# motordriver_control_board_02.net
KiCad netlist of a schematic drawn in EAGLE
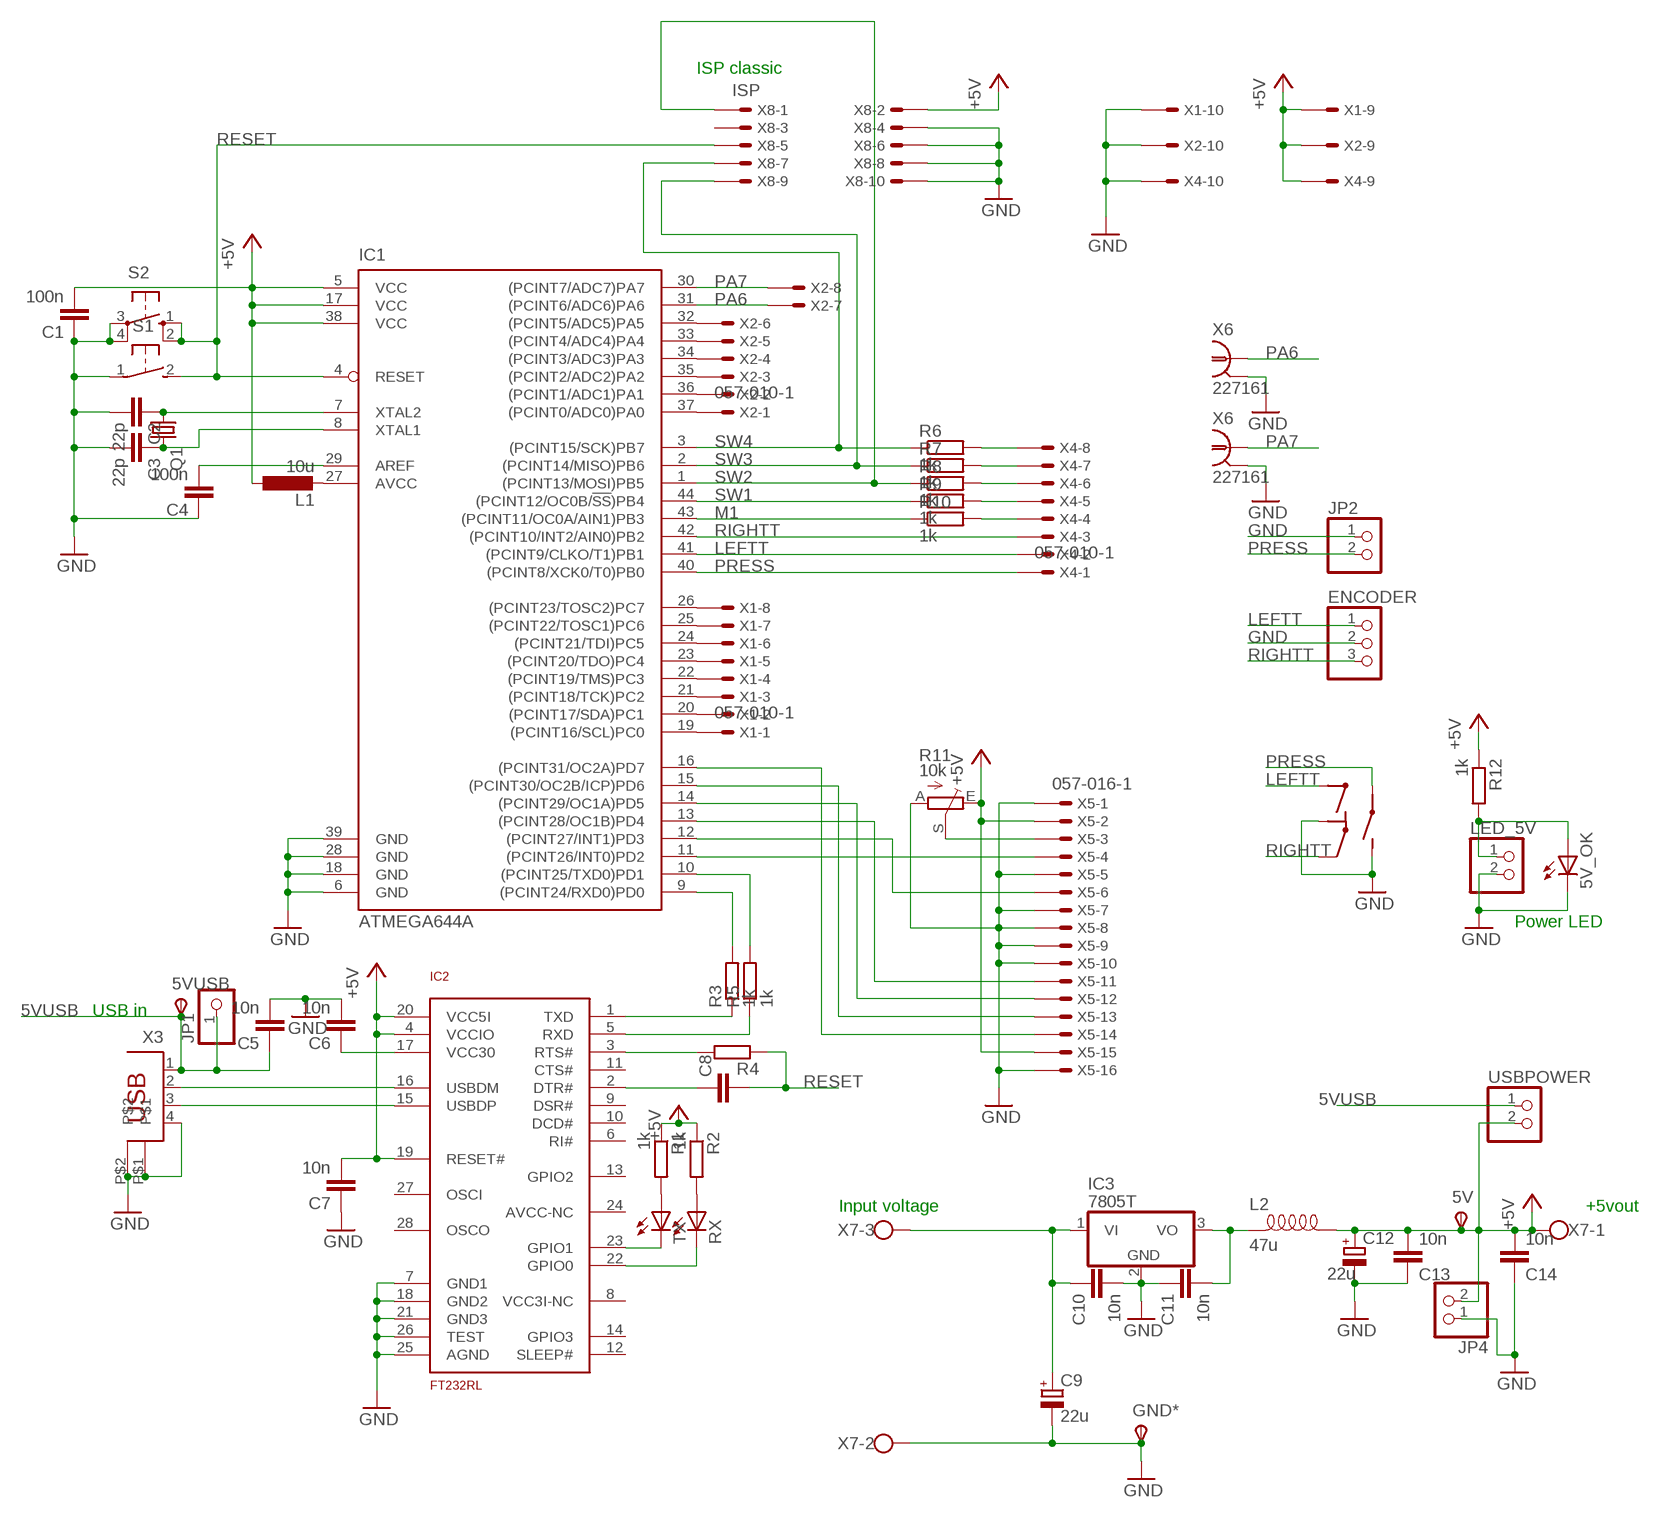
[diagram p0: schematic, sheet 1]

(export (version "E")
  (design (tool "Eeschema 10.0.6"))
  (components
    (comp (ref "5V")
      (value "TPSPAD1-13")
      (footprint "eagle-import:P1-13")
      (libsource (lib "eagle-import") (part "TPSPAD1-13"))
    )
    (comp (ref "5VUSB")
      (value "TPSPAD1-13")
      (footprint "eagle-import:P1-13")
      (libsource (lib "eagle-import") (part "TPSPAD1-13"))
    )
    (comp (ref "5V_OK")
      (value "ZURINO_LEDCHIP-LED0805")
      (footprint "eagle-import:ZURINO_CHIP-LED0805")
      (libsource (lib "eagle-import") (part "ZURINO_LEDCHIP-LED0805"))
    )
    (comp (ref "C1")
      (value "100n")
      (footprint "eagle-import:C0805")
      (libsource (lib "eagle-import") (part "C-EUC0805"))
    )
    (comp (ref "C2")
      (value "22p")
      (footprint "eagle-import:C0805")
      (libsource (lib "eagle-import") (part "C-EUC0805"))
    )
    (comp (ref "C3")
      (value "22p")
      (footprint "eagle-import:C0805")
      (libsource (lib "eagle-import") (part "C-EUC0805"))
    )
    (comp (ref "C4")
      (value "100n")
      (footprint "eagle-import:C0805")
      (libsource (lib "eagle-import") (part "C-EUC0805"))
    )
    (comp (ref "C5")
      (value "10n")
      (footprint "eagle-import:C0805")
      (libsource (lib "eagle-import") (part "C-EUC0805"))
    )
    (comp (ref "C6")
      (value "10n")
      (footprint "eagle-import:C0805")
      (libsource (lib "eagle-import") (part "C-EUC0805"))
    )
    (comp (ref "C7")
      (value "10n")
      (footprint "eagle-import:C0805")
      (libsource (lib "eagle-import") (part "C-EUC0805"))
    )
    (comp (ref "C8")
      (value "C-EUC0805")
      (footprint "eagle-import:C0805")
      (libsource (lib "eagle-import") (part "C-EUC0805"))
    )
    (comp (ref "C9")
      (value "22u")
      (footprint "eagle-import:153CLV-0605")
      (libsource (lib "eagle-import") (part "CPOL-EU153CLV-0605"))
    )
    (comp (ref "C10")
      (value "10n")
      (footprint "eagle-import:C0805")
      (libsource (lib "eagle-import") (part "C-EUC0805"))
    )
    (comp (ref "C11")
      (value "10n")
      (footprint "eagle-import:C0805")
      (libsource (lib "eagle-import") (part "C-EUC0805"))
    )
    (comp (ref "C12")
      (value "22u")
      (footprint "eagle-import:153CLV-0605")
      (libsource (lib "eagle-import") (part "CPOL-EU153CLV-0605"))
    )
    (comp (ref "C13")
      (value "10n")
      (footprint "eagle-import:C0805")
      (libsource (lib "eagle-import") (part "C-EUC0805"))
    )
    (comp (ref "C14")
      (value "10n")
      (footprint "eagle-import:C0805")
      (libsource (lib "eagle-import") (part "C-EUC0805"))
    )
    (comp (ref "ENCODER")
      (value "PINHD-1X3")
      (footprint "eagle-import:1X03")
      (libsource (lib "eagle-import") (part "PINHD-1X3"))
    )
    (comp (ref "GND*")
      (value "TPSPAD1-13")
      (footprint "eagle-import:P1-13")
      (libsource (lib "eagle-import") (part "TPSPAD1-13"))
    )
    (comp (ref "IC1")
      (value "ATMEGA644A")
      (footprint "eagle-import:TQFP44")
      (fields (field (name "MPN") "ATMEGA644PV-10AU"))
      (libsource (lib "eagle-import") (part "ATMEGA644A"))
    )
    (comp (ref "IC2")
      (value "FT232RL")
      (footprint "eagle-import:SMARTPRJ_SSOP28")
      (libsource (lib "eagle-import") (part "SMARTPRJ_FT232RL"))
    )
    (comp (ref "IC3")
      (value "7805T")
      (footprint "eagle-import:TO220H")
      (libsource (lib "eagle-import") (part "78T05"))
    )
    (comp (ref "JP1")
      (value "PINHD-1X1")
      (footprint "eagle-import:1X01")
      (libsource (lib "eagle-import") (part "PINHD-1X1"))
    )
    (comp (ref "JP2")
      (value "PINHD-1X2")
      (footprint "eagle-import:1X02")
      (libsource (lib "eagle-import") (part "PINHD-1X2"))
    )
    (comp (ref "JP4")
      (value "PINHD-1X2")
      (footprint "eagle-import:1X02")
      (libsource (lib "eagle-import") (part "PINHD-1X2"))
    )
    (comp (ref "L1")
      (value "10u")
      (footprint "eagle-import:L1812")
      (libsource (lib "eagle-import") (part "L-EUL1812"))
    )
    (comp (ref "L2")
      (value "47u")
      (footprint "eagle-import:D10F")
      (libsource (lib "eagle-import") (part "A814AY-220M"))
    )
    (comp (ref "LED_5V")
      (value "PINHD-1X2")
      (footprint "eagle-import:1X02")
      (libsource (lib "eagle-import") (part "PINHD-1X2"))
    )
    (comp (ref "Q1")
      (value "ZURINO_CRYSTALHC49UP")
      (footprint "eagle-import:ZURINO_HC49UP")
      (libsource (lib "eagle-import") (part "ZURINO_CRYSTALHC49UP"))
    )
    (comp (ref "R1")
      (value "1k")
      (footprint "eagle-import:M0805")
      (libsource (lib "eagle-import") (part "R-EU_M0805"))
    )
    (comp (ref "R2")
      (value "1k")
      (footprint "eagle-import:M0805")
      (libsource (lib "eagle-import") (part "R-EU_M0805"))
    )
    (comp (ref "R3")
      (value "1k")
      (footprint "eagle-import:M0805")
      (libsource (lib "eagle-import") (part "R-EU_M0805"))
    )
    (comp (ref "R4")
      (value "R-EU_M0805")
      (footprint "eagle-import:M0805")
      (libsource (lib "eagle-import") (part "R-EU_M0805"))
    )
    (comp (ref "R5")
      (value "1k")
      (footprint "eagle-import:M0805")
      (libsource (lib "eagle-import") (part "R-EU_M0805"))
    )
    (comp (ref "R6")
      (value "1k")
      (footprint "eagle-import:M0805")
      (libsource (lib "eagle-import") (part "R-EU_M0805"))
    )
    (comp (ref "R7")
      (value "1k")
      (footprint "eagle-import:M0805")
      (libsource (lib "eagle-import") (part "R-EU_M0805"))
    )
    (comp (ref "R8")
      (value "1k")
      (footprint "eagle-import:M0805")
      (libsource (lib "eagle-import") (part "R-EU_M0805"))
    )
    (comp (ref "R9")
      (value "1k")
      (footprint "eagle-import:M0805")
      (libsource (lib "eagle-import") (part "R-EU_M0805"))
    )
    (comp (ref "R10")
      (value "1k")
      (footprint "eagle-import:M0805")
      (libsource (lib "eagle-import") (part "R-EU_M0805"))
    )
    (comp (ref "R11")
      (value "10k")
      (footprint "eagle-import:B64Y")
      (libsource (lib "eagle-import") (part "TRIM_EU-B64Y"))
    )
    (comp (ref "R12")
      (value "1k")
      (footprint "eagle-import:M0805")
      (libsource (lib "eagle-import") (part "R-EU_M0805"))
    )
    (comp (ref "RX")
      (value "ZURINO_LEDCHIP-LED0805")
      (footprint "eagle-import:ZURINO_CHIP-LED0805")
      (libsource (lib "eagle-import") (part "ZURINO_LEDCHIP-LED0805"))
    )
    (comp (ref "S1")
      (value "ZURINO_31-XX")
      (footprint "eagle-import:ZURINO_OMRON_SW")
      (libsource (lib "eagle-import") (part "ZURINO_31-XX"))
    )
    (comp (ref "S2")
      (value "10-XX")
      (footprint "eagle-import:B3F-10XX")
      (fields (field (name "MPN") "B3F-1000"))
      (libsource (lib "eagle-import") (part "10-XX"))
    )
    (comp (ref "TX")
      (value "ZURINO_LEDCHIP-LED0805")
      (footprint "eagle-import:ZURINO_CHIP-LED0805")
      (libsource (lib "eagle-import") (part "ZURINO_LEDCHIP-LED0805"))
    )
    (comp (ref "U$1")
      (value "ENCODERW")
      (footprint "eagle-import:DREHENC")
      (libsource (lib "eagle-import") (part "ENCODERW"))
    )
    (comp (ref "USBPOWER")
      (value "PINHD-1X2")
      (footprint "eagle-import:1X02")
      (libsource (lib "eagle-import") (part "PINHD-1X2"))
    )
    (comp (ref "X1")
      (value "057-010-1")
      (footprint "eagle-import:057-010-1")
      (libsource (lib "eagle-import") (part "057-010-1"))
    )
    (comp (ref "X2")
      (value "057-010-1")
      (footprint "eagle-import:057-010-1")
      (libsource (lib "eagle-import") (part "057-010-1"))
    )
    (comp (ref "X3")
      (value "SMARTPRJ_PN61729")
      (footprint "eagle-import:SMARTPRJ_PN61729")
      (libsource (lib "eagle-import") (part "SMARTPRJ_PN61729"))
    )
    (comp (ref "X4")
      (value "057-010-1")
      (footprint "eagle-import:057-010-1")
      (libsource (lib "eagle-import") (part "057-010-1"))
    )
    (comp (ref "X5")
      (value "057-016-1")
      (footprint "eagle-import:057-016-1")
      (libsource (lib "eagle-import") (part "057-016-1"))
    )
    (comp (ref "X6")
      (value "227161")
      (footprint "eagle-import:AMP_227161")
      (libsource (lib "eagle-import") (part "227161"))
    )
    (comp (ref "X7")
      (value "W237-103")
      (footprint "eagle-import:W237-103")
      (fields (field (name "MPN") "237-103"))
      (libsource (lib "eagle-import") (part "W237-103"))
    )
    (comp (ref "X8")
      (value "ISP")
      (footprint "eagle-import:057-010-1")
      (libsource (lib "eagle-import") (part "057-010-1"))
    )
  )
  (nets
    (net (code "1") (name "+5V") (class "Default")
      (node (ref "5V") (pin "TP") (pinfunction "PP_TP") (pintype "input"))
      (node (ref "C1") (pin "2") (pinfunction "2_2") (pintype "passive"))
      (node (ref "C12") (pin "+") (pinfunction "+_+") (pintype "passive"))
      (node (ref "C13") (pin "2") (pinfunction "2_2") (pintype "passive"))
      (node (ref "C14") (pin "2") (pinfunction "2_2") (pintype "passive"))
      (node (ref "C7") (pin "2") (pinfunction "2_2") (pintype "passive"))
      (node (ref "IC1") (pin "17") (pinfunction "VCC_17") (pintype "power_in"))
      (node (ref "IC1") (pin "38") (pinfunction "VCC_38") (pintype "power_in"))
      (node (ref "IC1") (pin "5") (pinfunction "VCC_5") (pintype "power_in"))
      (node (ref "IC2") (pin "19") (pinfunction "RESET#_19") (pintype "input"))
      (node (ref "IC2") (pin "20") (pinfunction "VCC5I_20") (pintype "power_in"))
      (node (ref "IC2") (pin "4") (pinfunction "VCCIO_4") (pintype "power_in"))
      (node (ref "JP4") (pin "2") (pinfunction "2_2") (pintype "passive"))
      (node (ref "L1") (pin "1") (pinfunction "1_1") (pintype "passive"))
      (node (ref "L2") (pin "2") (pinfunction "2_2") (pintype "passive"))
      (node (ref "R1") (pin "1") (pinfunction "1_1") (pintype "passive"))
      (node (ref "R11") (pin "E") (pinfunction "E_E") (pintype "passive"))
      (node (ref "R12") (pin "1") (pinfunction "1_1") (pintype "passive"))
      (node (ref "R2") (pin "1") (pinfunction "1_1") (pintype "passive"))
      (node (ref "USBPOWER") (pin "2") (pinfunction "2_2") (pintype "passive"))
      (node (ref "X1") (pin "9") (pinfunction "S_9") (pintype "passive"))
      (node (ref "X2") (pin "9") (pinfunction "S_9") (pintype "passive"))
      (node (ref "X4") (pin "9") (pinfunction "S_9") (pintype "passive"))
      (node (ref "X5") (pin "15") (pinfunction "S_15") (pintype "passive"))
      (node (ref "X5") (pin "2") (pinfunction "S_2") (pintype "passive"))
      (node (ref "X7") (pin "1") (pinfunction "KL_1") (pintype "passive"))
      (node (ref "X8") (pin "2") (pinfunction "S_2") (pintype "passive"))
    )
    (net (code "2") (name "/5VUSB") (class "Default")
      (node (ref "5VUSB") (pin "TP") (pinfunction "PP_TP") (pintype "input"))
      (node (ref "C5") (pin "1") (pinfunction "1_1") (pintype "passive"))
      (node (ref "JP1") (pin "1") (pinfunction "1_1") (pintype "passive"))
      (node (ref "USBPOWER") (pin "1") (pinfunction "1_1") (pintype "passive"))
      (node (ref "X3") (pin "1") (pinfunction "1_1") (pintype "bidirectional"))
    )
    (net (code "3") (name "/LEFTT") (class "Default")
      (node (ref "ENCODER") (pin "1") (pinfunction "1_1") (pintype "passive"))
      (node (ref "IC1") (pin "41") (pinfunction "(PCINT9/CLKO/T1)PB1_41") (pintype "bidirectional"))
      (node (ref "U$1") (pin "P$1") (pinfunction "P$2_P$1") (pintype "bidirectional"))
      (node (ref "X4") (pin "2") (pinfunction "S_2") (pintype "passive"))
    )
    (net (code "4") (name "/M1") (class "Default")
      (node (ref "IC1") (pin "43") (pinfunction "(PCINT11/OC0A/AIN1)PB3_43") (pintype "bidirectional"))
      (node (ref "R10") (pin "1") (pinfunction "1_1") (pintype "passive"))
    )
    (net (code "5") (name "/PA6") (class "Default")
      (node (ref "IC1") (pin "31") (pinfunction "(PCINT6/ADC6)PA6_31") (pintype "bidirectional"))
      (node (ref "X2") (pin "7") (pinfunction "S_7") (pintype "passive"))
      (node (ref "X6") (pin "1") (pinfunction "1_1") (pintype "passive"))
    )
    (net (code "6") (name "/PA7") (class "Default")
      (node (ref "IC1") (pin "30") (pinfunction "(PCINT7/ADC7)PA7_30") (pintype "bidirectional"))
      (node (ref "X2") (pin "8") (pinfunction "S_8") (pintype "passive"))
      (node (ref "X6") (pin "2") (pinfunction "2_2") (pintype "passive"))
    )
    (net (code "7") (name "/PRESS") (class "Default")
      (node (ref "IC1") (pin "40") (pinfunction "(PCINT8/XCK0/T0)PB0_40") (pintype "bidirectional"))
      (node (ref "JP2") (pin "2") (pinfunction "2_2") (pintype "passive"))
      (node (ref "U$1") (pin "P$4") (pinfunction "P$4_P$4") (pintype "bidirectional"))
      (node (ref "X4") (pin "1") (pinfunction "S_1") (pintype "passive"))
    )
    (net (code "8") (name "/RESET") (class "Default")
      (node (ref "C8") (pin "2") (pinfunction "2_2") (pintype "passive"))
      (node (ref "IC1") (pin "4") (pinfunction "RESET_4") (pintype "input"))
      (node (ref "R4") (pin "1") (pinfunction "1_1") (pintype "passive"))
      (node (ref "S1") (pin "2") (pinfunction "S_2") (pintype "passive"))
      (node (ref "S2") (pin "1") (pinfunction "S_1") (pintype "passive"))
      (node (ref "S2") (pin "2") (pinfunction "S1_2") (pintype "passive"))
      (node (ref "X8") (pin "5") (pinfunction "S_5") (pintype "passive"))
    )
    (net (code "9") (name "/RIGHTT") (class "Default")
      (node (ref "ENCODER") (pin "3") (pinfunction "3_3") (pintype "passive"))
      (node (ref "IC1") (pin "42") (pinfunction "(PCINT10/INT2/AIN0)PB2_42") (pintype "bidirectional"))
      (node (ref "U$1") (pin "P$3") (pinfunction "P$3_P$3") (pintype "bidirectional"))
      (node (ref "X4") (pin "3") (pinfunction "S_3") (pintype "passive"))
    )
    (net (code "10") (name "/SW1") (class "Default")
      (node (ref "IC1") (pin "44") (pinfunction "(PCINT12/OC0B/~{SS})PB4_44") (pintype "bidirectional"))
      (node (ref "R9") (pin "1") (pinfunction "1_1") (pintype "passive"))
    )
    (net (code "11") (name "/SW2") (class "Default")
      (node (ref "IC1") (pin "1") (pinfunction "(PCINT13/MOSI)PB5_1") (pintype "bidirectional"))
      (node (ref "R8") (pin "1") (pinfunction "1_1") (pintype "passive"))
      (node (ref "X8") (pin "1") (pinfunction "S_1") (pintype "passive"))
    )
    (net (code "12") (name "/SW3") (class "Default")
      (node (ref "IC1") (pin "2") (pinfunction "(PCINT14/MISO)PB6_2") (pintype "bidirectional"))
      (node (ref "R7") (pin "1") (pinfunction "1_1") (pintype "passive"))
      (node (ref "X8") (pin "9") (pinfunction "S_9") (pintype "passive"))
    )
    (net (code "13") (name "/SW4") (class "Default")
      (node (ref "IC1") (pin "3") (pinfunction "(PCINT15/SCK)PB7_3") (pintype "bidirectional"))
      (node (ref "R6") (pin "1") (pinfunction "1_1") (pintype "passive"))
      (node (ref "X8") (pin "7") (pinfunction "S_7") (pintype "passive"))
    )
    (net (code "14") (name "GND") (class "Default")
      (node (ref "5V_OK") (pin "C") (pinfunction "C_C") (pintype "passive"))
      (node (ref "C1") (pin "1") (pinfunction "1_1") (pintype "passive"))
      (node (ref "C10") (pin "2") (pinfunction "2_2") (pintype "passive"))
      (node (ref "C11") (pin "1") (pinfunction "1_1") (pintype "passive"))
      (node (ref "C12") (pin "-") (pinfunction "-_-") (pintype "passive"))
      (node (ref "C13") (pin "1") (pinfunction "1_1") (pintype "passive"))
      (node (ref "C14") (pin "1") (pinfunction "1_1") (pintype "passive"))
      (node (ref "C2") (pin "2") (pinfunction "2_2") (pintype "passive"))
      (node (ref "C3") (pin "2") (pinfunction "2_2") (pintype "passive"))
      (node (ref "C4") (pin "1") (pinfunction "1_1") (pintype "passive"))
      (node (ref "C5") (pin "2") (pinfunction "2_2") (pintype "passive"))
      (node (ref "C6") (pin "2") (pinfunction "2_2") (pintype "passive"))
      (node (ref "C7") (pin "1") (pinfunction "1_1") (pintype "passive"))
      (node (ref "C9") (pin "-") (pinfunction "-_-") (pintype "passive"))
      (node (ref "ENCODER") (pin "2") (pinfunction "2_2") (pintype "passive"))
      (node (ref "GND*") (pin "TP") (pinfunction "PP_TP") (pintype "input"))
      (node (ref "IC1") (pin "18") (pinfunction "GND_18") (pintype "power_in"))
      (node (ref "IC1") (pin "28") (pinfunction "GND_28") (pintype "power_in"))
      (node (ref "IC1") (pin "39") (pinfunction "GND_39") (pintype "power_in"))
      (node (ref "IC1") (pin "6") (pinfunction "GND_6") (pintype "power_in"))
      (node (ref "IC2") (pin "18") (pinfunction "GND2_18") (pintype "power_in"))
      (node (ref "IC2") (pin "21") (pinfunction "GND3_21") (pintype "power_in"))
      (node (ref "IC2") (pin "25") (pinfunction "AGND_25") (pintype "power_in"))
      (node (ref "IC2") (pin "26") (pinfunction "TEST_26") (pintype "input"))
      (node (ref "IC2") (pin "7") (pinfunction "GND1_7") (pintype "power_in"))
      (node (ref "IC3") (pin "2") (pinfunction "GND_2") (pintype "passive"))
      (node (ref "JP2") (pin "1") (pinfunction "1_1") (pintype "passive"))
      (node (ref "JP4") (pin "1") (pinfunction "1_1") (pintype "passive"))
      (node (ref "LED_5V") (pin "2") (pinfunction "2_2") (pintype "passive"))
      (node (ref "R11") (pin "A") (pinfunction "A_A") (pintype "passive"))
      (node (ref "S1") (pin "1") (pinfunction "P_1") (pintype "passive"))
      (node (ref "S2") (pin "3") (pinfunction "P_3") (pintype "passive"))
      (node (ref "S2") (pin "4") (pinfunction "P1_4") (pintype "passive"))
      (node (ref "U$1") (pin "P$2") (pinfunction "P$1_P$2") (pintype "bidirectional"))
      (node (ref "U$1") (pin "P$5") (pinfunction "P$5_P$5") (pintype "bidirectional"))
      (node (ref "X1") (pin "10") (pinfunction "S_10") (pintype "passive"))
      (node (ref "X2") (pin "10") (pinfunction "S_10") (pintype "passive"))
      (node (ref "X3") (pin "4") (pinfunction "4_4") (pintype "bidirectional"))
      (node (ref "X3") (pin "P$1") (pinfunction "P$1_P$1") (pintype "bidirectional"))
      (node (ref "X3") (pin "P$2") (pinfunction "P$2_P$2") (pintype "bidirectional"))
      (node (ref "X4") (pin "10") (pinfunction "S_10") (pintype "passive"))
      (node (ref "X5") (pin "1") (pinfunction "S_1") (pintype "passive"))
      (node (ref "X5") (pin "10") (pinfunction "S_10") (pintype "passive"))
      (node (ref "X5") (pin "16") (pinfunction "S_16") (pintype "passive"))
      (node (ref "X5") (pin "5") (pinfunction "S_5") (pintype "passive"))
      (node (ref "X5") (pin "7") (pinfunction "S_7") (pintype "passive"))
      (node (ref "X5") (pin "8") (pinfunction "S_8") (pintype "passive"))
      (node (ref "X5") (pin "9") (pinfunction "S_9") (pintype "passive"))
      (node (ref "X6") (pin "1_GND") (pinfunction "1_GND_1_GND") (pintype "passive"))
      (node (ref "X6") (pin "2_GND") (pinfunction "2_GND_2_GND") (pintype "passive"))
      (node (ref "X7") (pin "2") (pinfunction "KL_2") (pintype "passive"))
      (node (ref "X8") (pin "10") (pinfunction "S_10") (pintype "passive"))
      (node (ref "X8") (pin "4") (pinfunction "S_4") (pintype "passive"))
      (node (ref "X8") (pin "6") (pinfunction "S_6") (pintype "passive"))
      (node (ref "X8") (pin "8") (pinfunction "S_8") (pintype "passive"))
    )
    (net (code "15") (name "Net-(5V_OK-PadA)") (class "Default")
      (node (ref "5V_OK") (pin "A") (pinfunction "A_A") (pintype "passive"))
      (node (ref "LED_5V") (pin "1") (pinfunction "1_1") (pintype "passive"))
      (node (ref "R12") (pin "2") (pinfunction "2_2") (pintype "passive"))
    )
    (net (code "16") (name "Net-(IC1-(PCINT0{slash}ADC0)PA0)") (class "Default")
      (node (ref "IC1") (pin "37") (pinfunction "(PCINT0/ADC0)PA0_37") (pintype "bidirectional"))
      (node (ref "X2") (pin "1") (pinfunction "S_1") (pintype "passive"))
    )
    (net (code "17") (name "Net-(IC1-(PCINT1{slash}ADC1)PA1)") (class "Default")
      (node (ref "IC1") (pin "36") (pinfunction "(PCINT1/ADC1)PA1_36") (pintype "bidirectional"))
      (node (ref "X2") (pin "2") (pinfunction "S_2") (pintype "passive"))
    )
    (net (code "18") (name "Net-(IC1-(PCINT2{slash}ADC2)PA2)") (class "Default")
      (node (ref "IC1") (pin "35") (pinfunction "(PCINT2/ADC2)PA2_35") (pintype "bidirectional"))
      (node (ref "X2") (pin "3") (pinfunction "S_3") (pintype "passive"))
    )
    (net (code "19") (name "Net-(IC1-(PCINT3{slash}ADC3)PA3)") (class "Default")
      (node (ref "IC1") (pin "34") (pinfunction "(PCINT3/ADC3)PA3_34") (pintype "bidirectional"))
      (node (ref "X2") (pin "4") (pinfunction "S_4") (pintype "passive"))
    )
    (net (code "20") (name "Net-(IC1-(PCINT4{slash}ADC4)PA4)") (class "Default")
      (node (ref "IC1") (pin "33") (pinfunction "(PCINT4/ADC4)PA4_33") (pintype "bidirectional"))
      (node (ref "X2") (pin "5") (pinfunction "S_5") (pintype "passive"))
    )
    (net (code "21") (name "Net-(IC1-(PCINT5{slash}ADC5)PA5)") (class "Default")
      (node (ref "IC1") (pin "32") (pinfunction "(PCINT5/ADC5)PA5_32") (pintype "bidirectional"))
      (node (ref "X2") (pin "6") (pinfunction "S_6") (pintype "passive"))
    )
    (net (code "22") (name "Net-(IC1-(PCINT16{slash}SCL)PC0)") (class "Default")
      (node (ref "IC1") (pin "19") (pinfunction "(PCINT16/SCL)PC0_19") (pintype "output"))
      (node (ref "X1") (pin "1") (pinfunction "S_1") (pintype "passive"))
    )
    (net (code "23") (name "Net-(IC1-(PCINT17{slash}SDA)PC1)") (class "Default")
      (node (ref "IC1") (pin "20") (pinfunction "(PCINT17/SDA)PC1_20") (pintype "output"))
      (node (ref "X1") (pin "2") (pinfunction "S_2") (pintype "passive"))
    )
    (net (code "24") (name "Net-(IC1-(PCINT18{slash}TCK)PC2)") (class "Default")
      (node (ref "IC1") (pin "21") (pinfunction "(PCINT18/TCK)PC2_21") (pintype "output"))
      (node (ref "X1") (pin "3") (pinfunction "S_3") (pintype "passive"))
    )
    (net (code "25") (name "Net-(IC1-(PCINT19{slash}TMS)PC3)") (class "Default")
      (node (ref "IC1") (pin "22") (pinfunction "(PCINT19/TMS)PC3_22") (pintype "output"))
      (node (ref "X1") (pin "4") (pinfunction "S_4") (pintype "passive"))
    )
    (net (code "26") (name "Net-(IC1-(PCINT20{slash}TDO)PC4)") (class "Default")
      (node (ref "IC1") (pin "23") (pinfunction "(PCINT20/TDO)PC4_23") (pintype "output"))
      (node (ref "X1") (pin "5") (pinfunction "S_5") (pintype "passive"))
    )
    (net (code "27") (name "Net-(IC1-(PCINT21{slash}TDI)PC5)") (class "Default")
      (node (ref "IC1") (pin "24") (pinfunction "(PCINT21/TDI)PC5_24") (pintype "output"))
      (node (ref "X1") (pin "6") (pinfunction "S_6") (pintype "passive"))
    )
    (net (code "28") (name "Net-(IC1-(PCINT22{slash}TOSC1)PC6)") (class "Default")
      (node (ref "IC1") (pin "25") (pinfunction "(PCINT22/TOSC1)PC6_25") (pintype "output"))
      (node (ref "X1") (pin "7") (pinfunction "S_7") (pintype "passive"))
    )
    (net (code "29") (name "Net-(IC1-(PCINT23{slash}TOSC2)PC7)") (class "Default")
      (node (ref "IC1") (pin "26") (pinfunction "(PCINT23/TOSC2)PC7_26") (pintype "output"))
      (node (ref "X1") (pin "8") (pinfunction "S_8") (pintype "passive"))
    )
    (net (code "30") (name "Net-(IC1-(PCINT24{slash}RXD0)PD0)") (class "Default")
      (node (ref "IC1") (pin "9") (pinfunction "(PCINT24/RXD0)PD0_9") (pintype "bidirectional"))
      (node (ref "R3") (pin "2") (pinfunction "2_2") (pintype "passive"))
    )
    (net (code "31") (name "Net-(IC1-(PCINT25{slash}TXD0)PD1)") (class "Default")
      (node (ref "IC1") (pin "10") (pinfunction "(PCINT25/TXD0)PD1_10") (pintype "bidirectional"))
      (node (ref "R5") (pin "2") (pinfunction "2_2") (pintype "passive"))
    )
    (net (code "32") (name "Net-(IC1-(PCINT26{slash}INT0)PD2)") (class "Default")
      (node (ref "IC1") (pin "11") (pinfunction "(PCINT26/INT0)PD2_11") (pintype "bidirectional"))
      (node (ref "X5") (pin "4") (pinfunction "S_4") (pintype "passive"))
    )
    (net (code "33") (name "Net-(IC1-(PCINT27{slash}INT1)PD3)") (class "Default")
      (node (ref "IC1") (pin "12") (pinfunction "(PCINT27/INT1)PD3_12") (pintype "bidirectional"))
      (node (ref "X5") (pin "6") (pinfunction "S_6") (pintype "passive"))
    )
    (net (code "34") (name "Net-(IC1-(PCINT28{slash}OC1B)PD4)") (class "Default")
      (node (ref "IC1") (pin "13") (pinfunction "(PCINT28/OC1B)PD4_13") (pintype "bidirectional"))
      (node (ref "X5") (pin "11") (pinfunction "S_11") (pintype "passive"))
    )
    (net (code "35") (name "Net-(IC1-(PCINT29{slash}OC1A)PD5)") (class "Default")
      (node (ref "IC1") (pin "14") (pinfunction "(PCINT29/OC1A)PD5_14") (pintype "bidirectional"))
      (node (ref "X5") (pin "12") (pinfunction "S_12") (pintype "passive"))
    )
    (net (code "36") (name "Net-(IC1-(PCINT30{slash}OC2B{slash}ICP)PD6)") (class "Default")
      (node (ref "IC1") (pin "15") (pinfunction "(PCINT30/OC2B/ICP)PD6_15") (pintype "bidirectional"))
      (node (ref "X5") (pin "13") (pinfunction "S_13") (pintype "passive"))
    )
    (net (code "37") (name "Net-(IC1-(PCINT31{slash}OC2A)PD7)") (class "Default")
      (node (ref "IC1") (pin "16") (pinfunction "(PCINT31/OC2A)PD7_16") (pintype "bidirectional"))
      (node (ref "X5") (pin "14") (pinfunction "S_14") (pintype "passive"))
    )
    (net (code "38") (name "Net-(IC1-AREF)") (class "Default")
      (node (ref "C4") (pin "2") (pinfunction "2_2") (pintype "passive"))
      (node (ref "IC1") (pin "29") (pinfunction "AREF_29") (pintype "passive"))
    )
    (net (code "39") (name "Net-(IC1-AVCC)") (class "Default")
      (node (ref "IC1") (pin "27") (pinfunction "AVCC_27") (pintype "power_in"))
      (node (ref "L1") (pin "2") (pinfunction "2_2") (pintype "passive"))
    )
    (net (code "40") (name "Net-(IC1-XTAL1)") (class "Default")
      (node (ref "C3") (pin "1") (pinfunction "1_1") (pintype "passive"))
      (node (ref "IC1") (pin "8") (pinfunction "XTAL1_8") (pintype "bidirectional"))
      (node (ref "Q1") (pin "2") (pinfunction "2_2") (pintype "passive"))
    )
    (net (code "41") (name "Net-(IC1-XTAL2)") (class "Default")
      (node (ref "C2") (pin "1") (pinfunction "1_1") (pintype "passive"))
      (node (ref "IC1") (pin "7") (pinfunction "XTAL2_7") (pintype "bidirectional"))
      (node (ref "Q1") (pin "1") (pinfunction "1_1") (pintype "passive"))
    )
    (net (code "42") (name "Net-(IC2-DTR#)") (class "Default")
      (node (ref "C8") (pin "1") (pinfunction "1_1") (pintype "passive"))
      (node (ref "IC2") (pin "2") (pinfunction "DTR#_2") (pintype "output"))
    )
    (net (code "43") (name "Net-(IC2-GPIO0)") (class "Default")
      (node (ref "IC2") (pin "22") (pinfunction "GPIO0_22") (pintype "output"))
      (node (ref "RX") (pin "C") (pinfunction "C_C") (pintype "passive"))
    )
    (net (code "44") (name "Net-(IC2-GPIO1)") (class "Default")
      (node (ref "IC2") (pin "23") (pinfunction "GPIO1_23") (pintype "output"))
      (node (ref "TX") (pin "C") (pinfunction "C_C") (pintype "passive"))
    )
    (net (code "45") (name "Net-(IC2-RTS#)") (class "Default")
      (node (ref "IC2") (pin "3") (pinfunction "RTS#_3") (pintype "output"))
      (node (ref "R4") (pin "2") (pinfunction "2_2") (pintype "passive"))
    )
    (net (code "46") (name "Net-(IC2-RXD)") (class "Default")
      (node (ref "IC2") (pin "5") (pinfunction "RXD_5") (pintype "input"))
      (node (ref "R5") (pin "1") (pinfunction "1_1") (pintype "passive"))
    )
    (net (code "47") (name "Net-(IC2-TXD)") (class "Default")
      (node (ref "IC2") (pin "1") (pinfunction "TXD_1") (pintype "output"))
      (node (ref "R3") (pin "1") (pinfunction "1_1") (pintype "passive"))
    )
    (net (code "48") (name "Net-(IC2-USBDM)") (class "Default")
      (node (ref "IC2") (pin "16") (pinfunction "USBDM_16") (pintype "bidirectional"))
      (node (ref "X3") (pin "2") (pinfunction "2_2") (pintype "bidirectional"))
    )
    (net (code "49") (name "Net-(IC2-USBDP)") (class "Default")
      (node (ref "IC2") (pin "15") (pinfunction "USBDP_15") (pintype "bidirectional"))
      (node (ref "X3") (pin "3") (pinfunction "3_3") (pintype "bidirectional"))
    )
    (net (code "50") (name "Net-(IC2-VCC30)") (class "Default")
      (node (ref "C6") (pin "1") (pinfunction "1_1") (pintype "passive"))
      (node (ref "IC2") (pin "17") (pinfunction "VCC30_17") (pintype "power_in"))
    )
    (net (code "51") (name "Net-(IC3-VI)") (class "Default")
      (node (ref "C10") (pin "1") (pinfunction "1_1") (pintype "passive"))
      (node (ref "C9") (pin "+") (pinfunction "+_+") (pintype "passive"))
      (node (ref "IC3") (pin "1") (pinfunction "VI_1") (pintype "input"))
      (node (ref "X7") (pin "3") (pinfunction "KL_3") (pintype "passive"))
    )
    (net (code "52") (name "Net-(IC3-VO)") (class "Default")
      (node (ref "C11") (pin "2") (pinfunction "2_2") (pintype "passive"))
      (node (ref "IC3") (pin "3") (pinfunction "VO_3") (pintype "passive"))
      (node (ref "L2") (pin "1") (pinfunction "1_1") (pintype "passive"))
    )
    (net (code "53") (name "Net-(R1-Pad2)") (class "Default")
      (node (ref "R1") (pin "2") (pinfunction "2_2") (pintype "passive"))
      (node (ref "TX") (pin "A") (pinfunction "A_A") (pintype "passive"))
    )
    (net (code "54") (name "Net-(R2-Pad2)") (class "Default")
      (node (ref "R2") (pin "2") (pinfunction "2_2") (pintype "passive"))
      (node (ref "RX") (pin "A") (pinfunction "A_A") (pintype "passive"))
    )
    (net (code "55") (name "Net-(X4E-S)") (class "Default")
      (node (ref "R10") (pin "2") (pinfunction "2_2") (pintype "passive"))
      (node (ref "X4") (pin "4") (pinfunction "S_4") (pintype "passive"))
    )
    (net (code "56") (name "Net-(X4F-S)") (class "Default")
      (node (ref "R9") (pin "2") (pinfunction "2_2") (pintype "passive"))
      (node (ref "X4") (pin "5") (pinfunction "S_5") (pintype "passive"))
    )
    (net (code "57") (name "Net-(X4G-S)") (class "Default")
      (node (ref "R8") (pin "2") (pinfunction "2_2") (pintype "passive"))
      (node (ref "X4") (pin "6") (pinfunction "S_6") (pintype "passive"))
    )
    (net (code "58") (name "Net-(X4H-S)") (class "Default")
      (node (ref "R7") (pin "2") (pinfunction "2_2") (pintype "passive"))
      (node (ref "X4") (pin "7") (pinfunction "S_7") (pintype "passive"))
    )
    (net (code "59") (name "Net-(X4I-S)") (class "Default")
      (node (ref "R6") (pin "2") (pinfunction "2_2") (pintype "passive"))
      (node (ref "X4") (pin "8") (pinfunction "S_8") (pintype "passive"))
    )
    (net (code "60") (name "Net-(X5J-S)") (class "Default")
      (node (ref "R11") (pin "S") (pinfunction "S_S") (pintype "passive"))
      (node (ref "X5") (pin "3") (pinfunction "S_3") (pintype "passive"))
    )
    (net (code "61") (name "unconnected-(IC2-AVCC-NC-Pad24)") (class "Default")
      (node (ref "IC2") (pin "24") (pinfunction "AVCC-NC_24") (pintype "no_connect"))
    )
    (net (code "62") (name "unconnected-(IC2-CTS#-Pad11)") (class "Default")
      (node (ref "IC2") (pin "11") (pinfunction "CTS#_11") (pintype "input"))
    )
    (net (code "63") (name "unconnected-(IC2-DCD#-Pad10)") (class "Default")
      (node (ref "IC2") (pin "10") (pinfunction "DCD#_10") (pintype "input"))
    )
    (net (code "64") (name "unconnected-(IC2-DSR#-Pad9)") (class "Default")
      (node (ref "IC2") (pin "9") (pinfunction "DSR#_9") (pintype "input"))
    )
    (net (code "65") (name "unconnected-(IC2-GPIO2-Pad13)") (class "Default")
      (node (ref "IC2") (pin "13") (pinfunction "GPIO2_13") (pintype "output"))
    )
    (net (code "66") (name "unconnected-(IC2-GPIO3-Pad14)") (class "Default")
      (node (ref "IC2") (pin "14") (pinfunction "GPIO3_14") (pintype "input"))
    )
    (net (code "67") (name "unconnected-(IC2-OSCI-Pad27)") (class "Default")
      (node (ref "IC2") (pin "27") (pinfunction "OSCI_27") (pintype "input"))
    )
    (net (code "68") (name "unconnected-(IC2-OSCO-Pad28)") (class "Default")
      (node (ref "IC2") (pin "28") (pinfunction "OSCO_28") (pintype "output"))
    )
    (net (code "69") (name "unconnected-(IC2-RI#-Pad6)") (class "Default")
      (node (ref "IC2") (pin "6") (pinfunction "RI#_6") (pintype "input"))
    )
    (net (code "70") (name "unconnected-(IC2-SLEEP#-Pad12)") (class "Default")
      (node (ref "IC2") (pin "12") (pinfunction "SLEEP#_12") (pintype "input"))
    )
    (net (code "71") (name "unconnected-(IC2-VCC3I-NC-Pad8)") (class "Default")
      (node (ref "IC2") (pin "8") (pinfunction "VCC3I-NC_8") (pintype "no_connect"))
    )
    (net (code "72") (name "unconnected-(X8D-S-Pad3)") (class "Default")
      (node (ref "X8") (pin "3") (pinfunction "S_3") (pintype "passive"))
    )
  )
)
